# Sheet1.net
KiCad netlist of a schematic drawn in Altium Designer
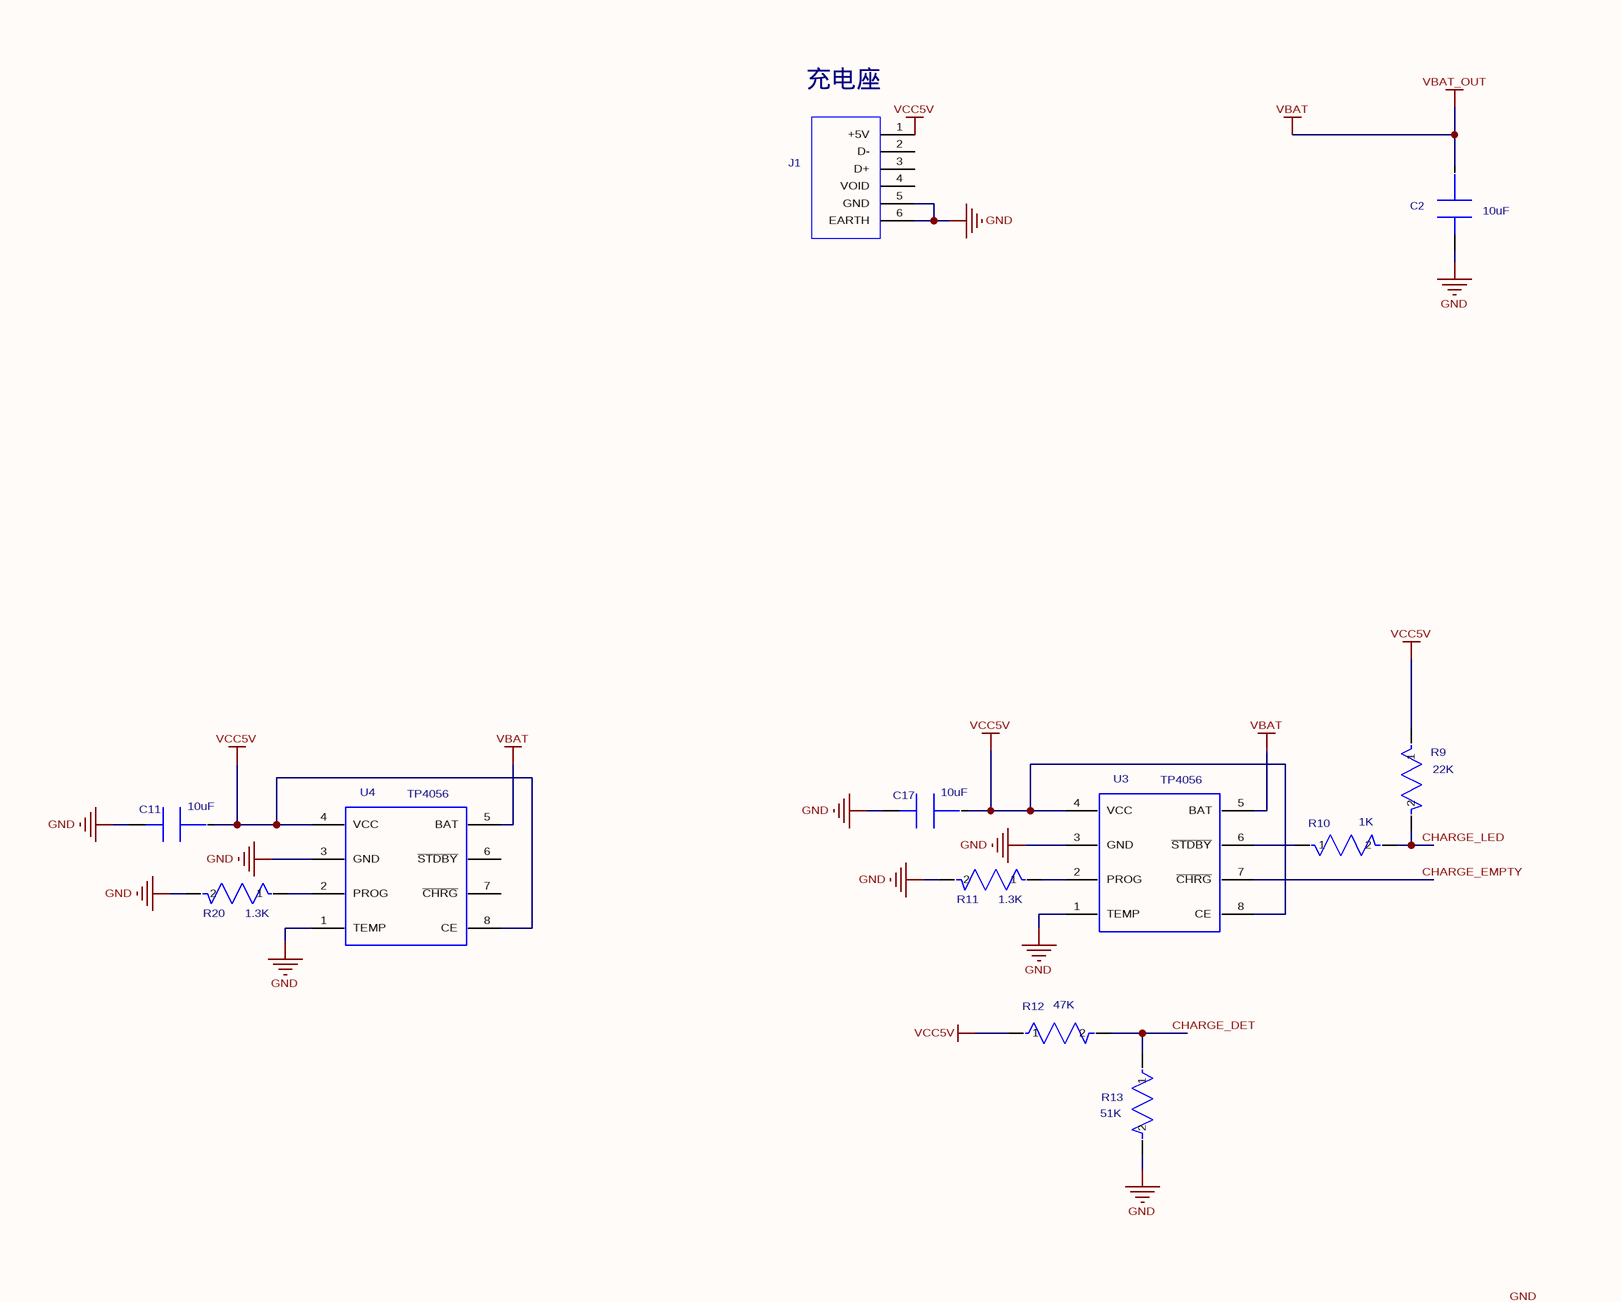
[diagram p0: Sheet1.SchDoc, top column 1 of 4]
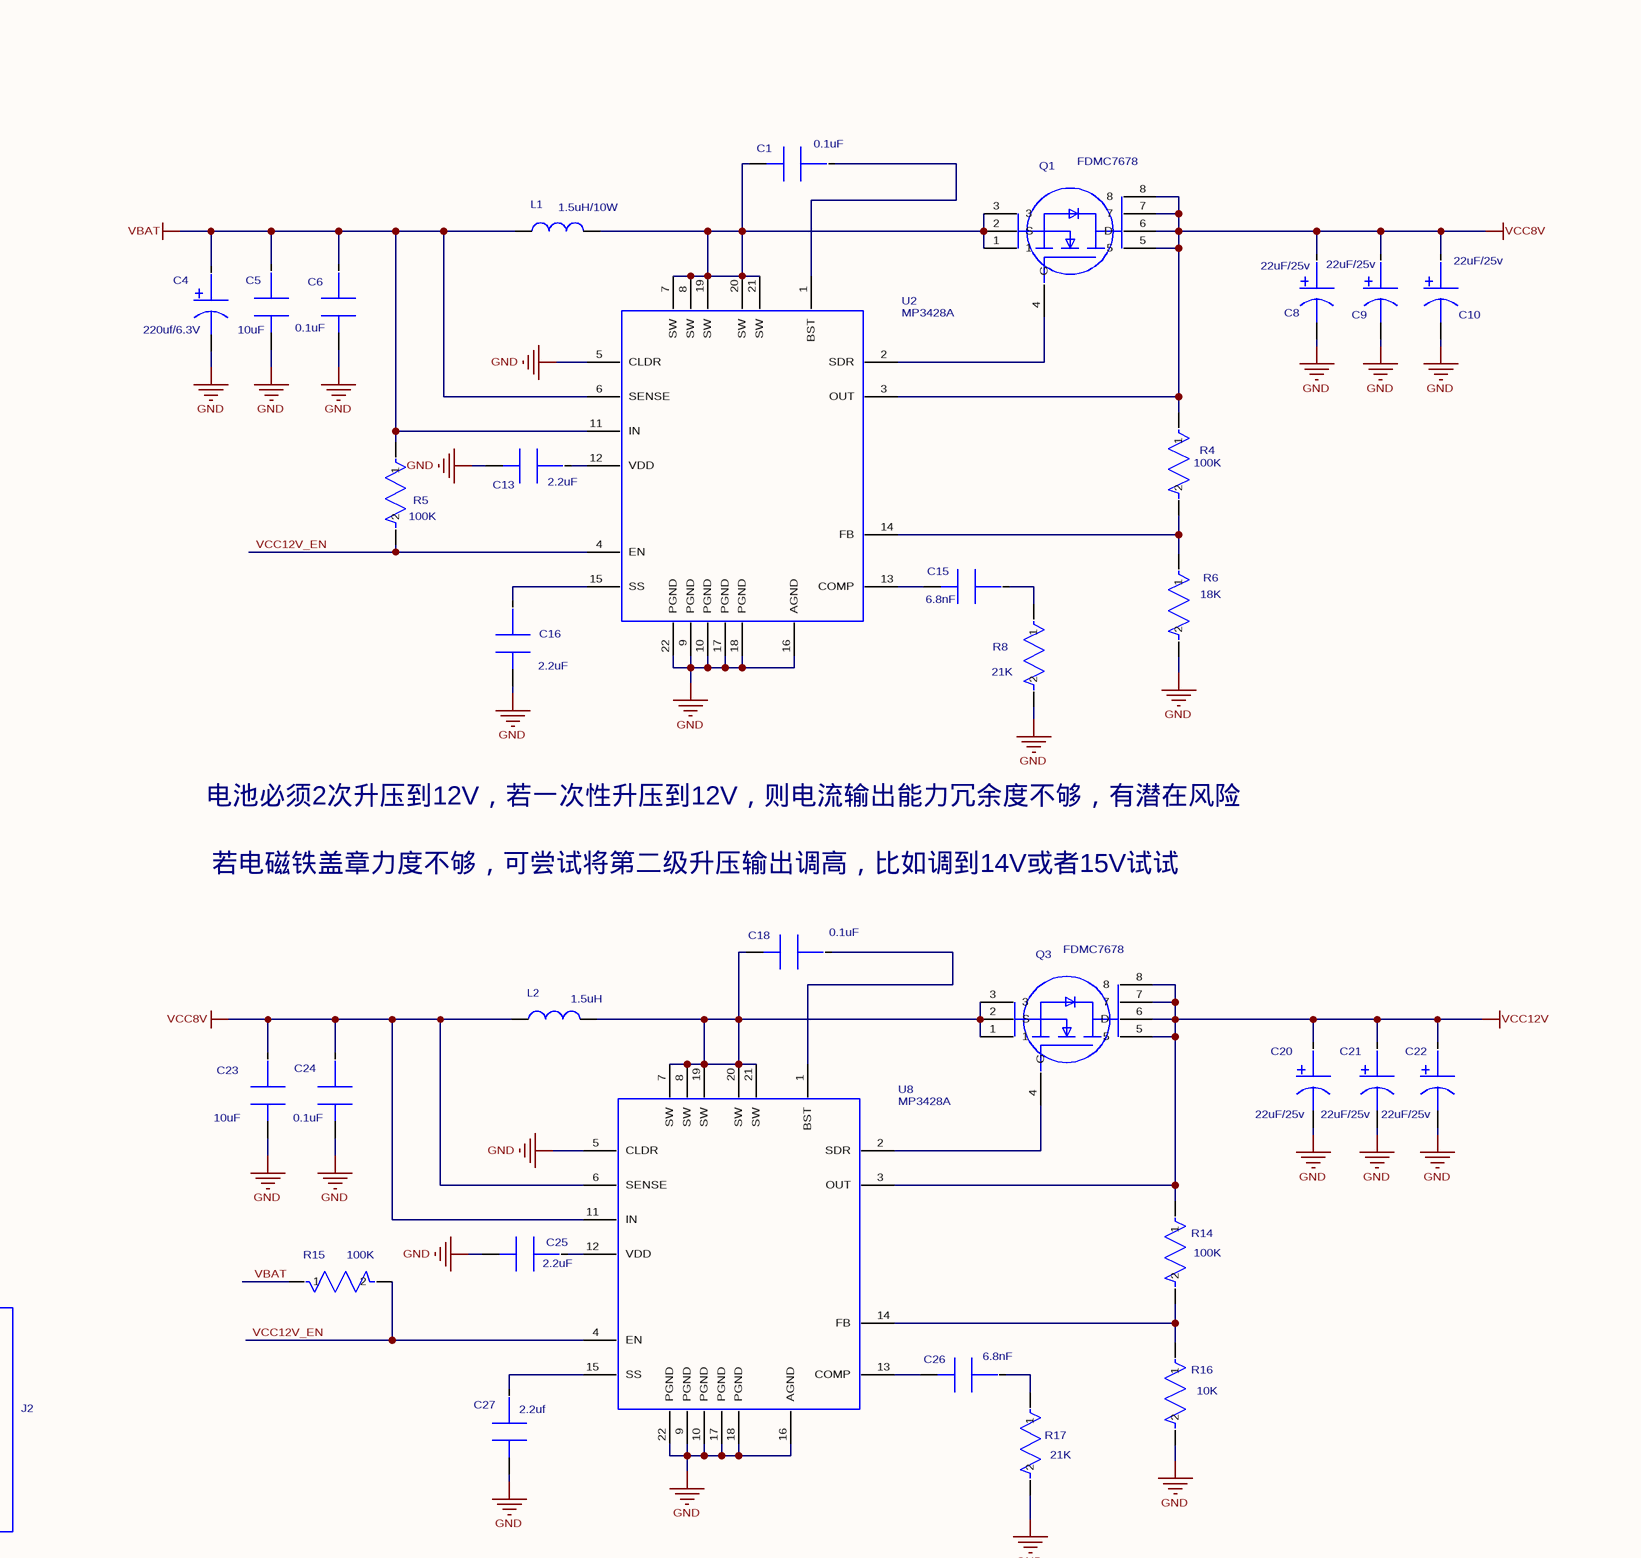
[diagram p1: Sheet1.SchDoc, top column 2 of 4]
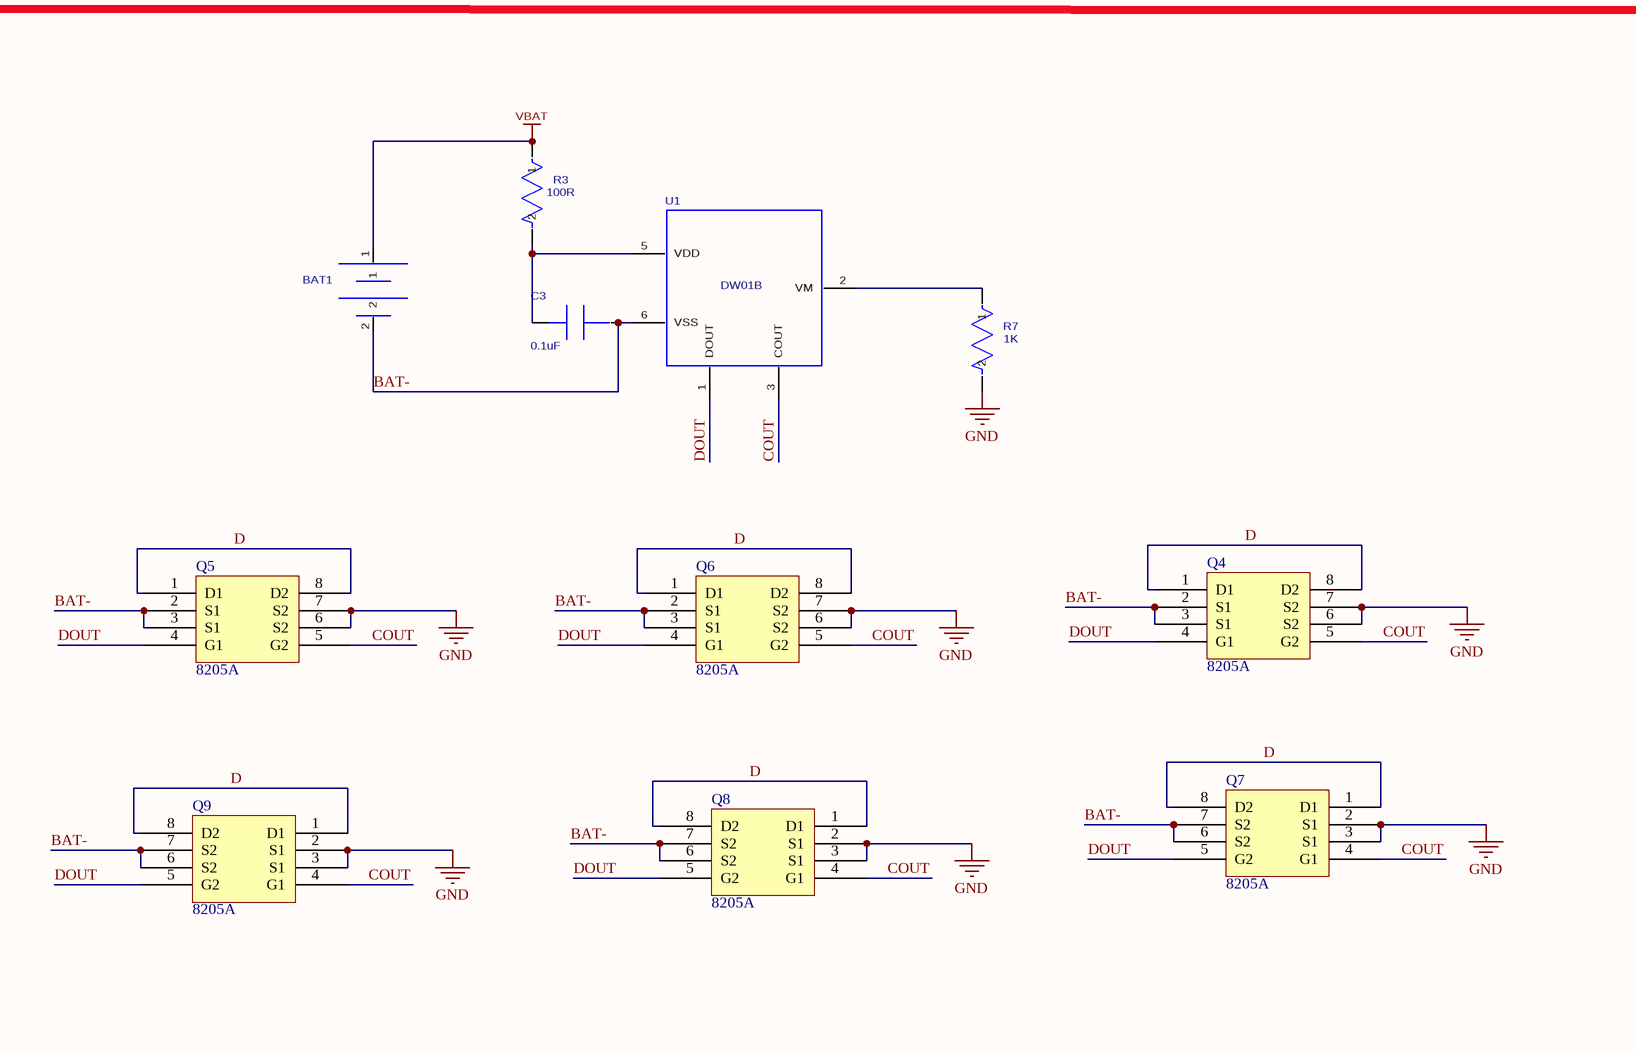
[diagram p2: Sheet1.SchDoc, top column 4 of 4]
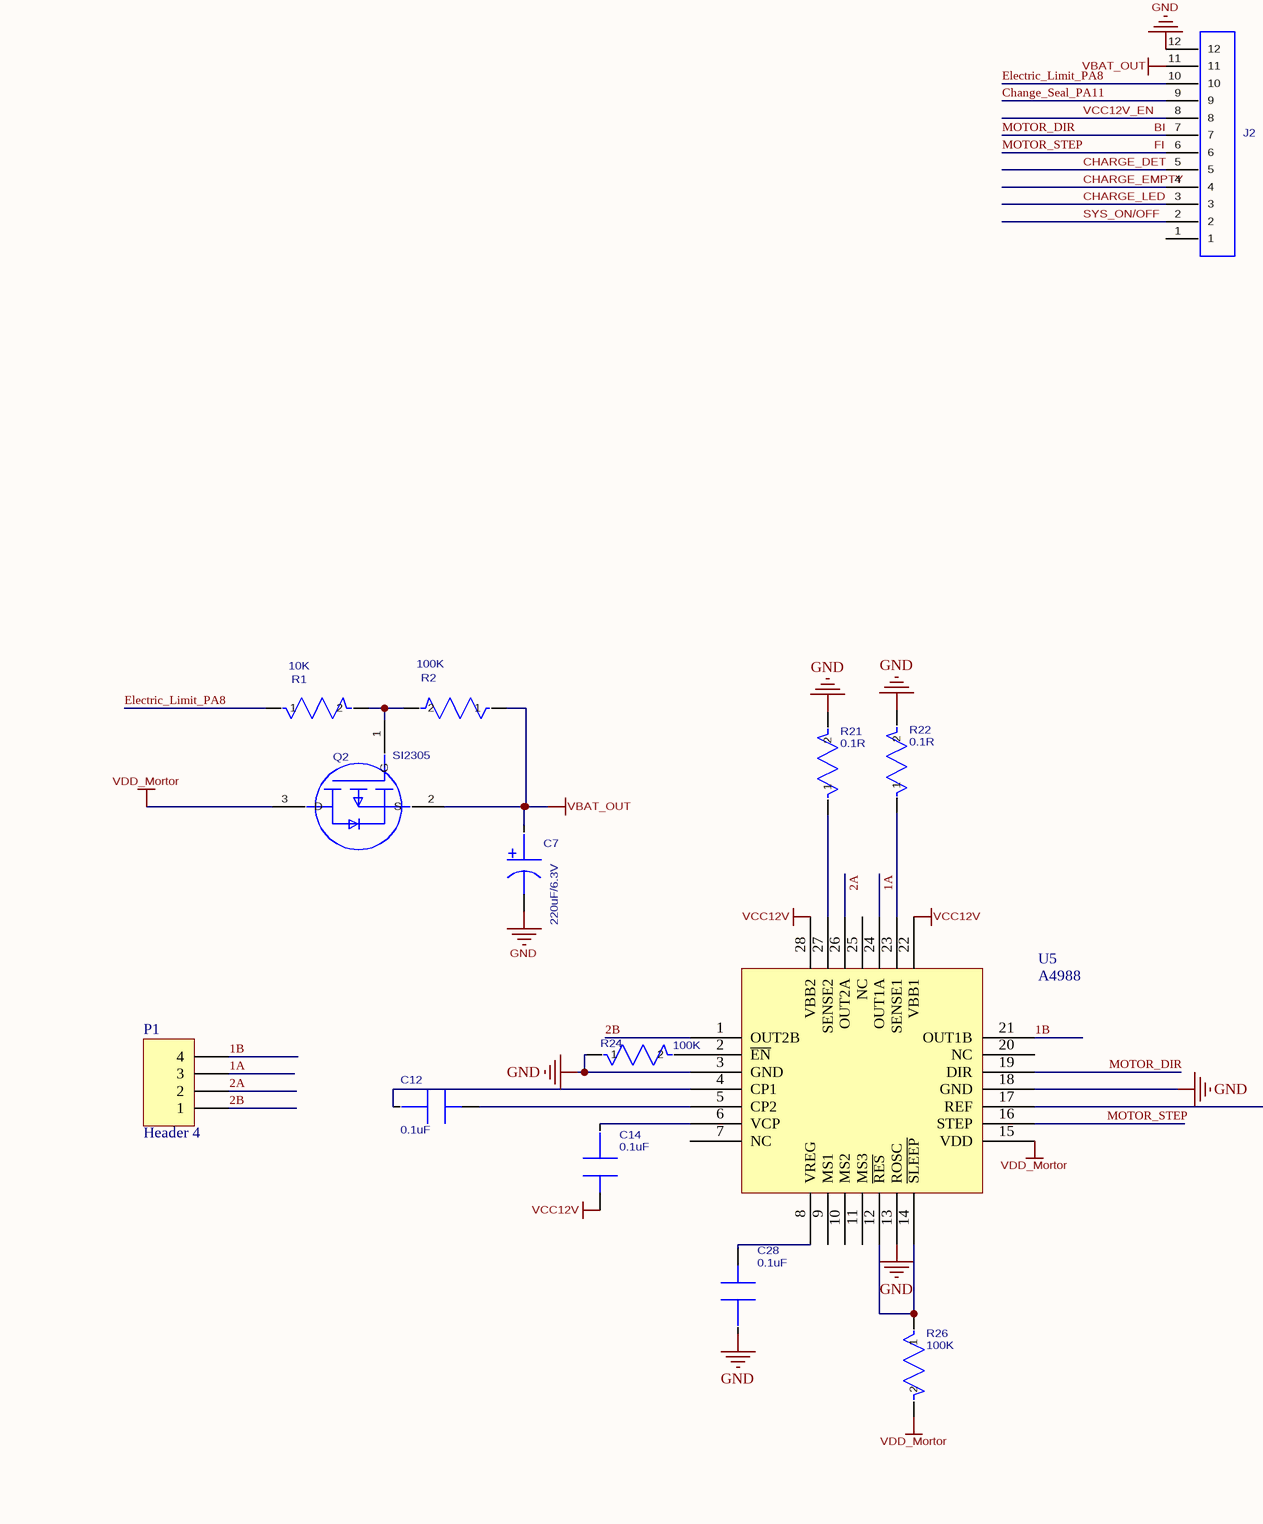
[diagram p3: Sheet1.SchDoc, bottom column 1 of 4]
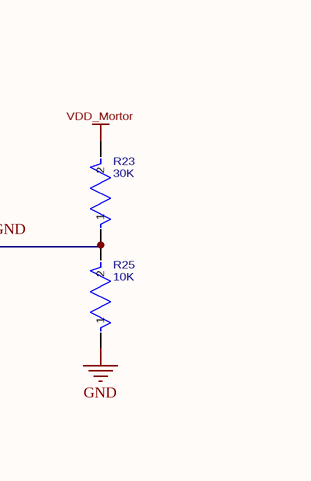
[diagram p4: Sheet1.SchDoc, bottom column 2 of 4]
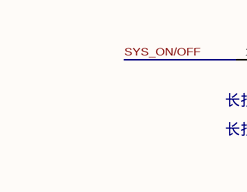
[diagram p5: Sheet1.SchDoc, bottom column 3 of 4]
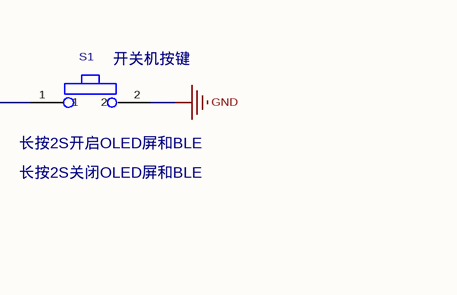
[diagram p6: Sheet1.SchDoc, bottom column 4 of 4]

(export (version "E")
  (design (tool "Eeschema 10.0.6"))
  (components
    (comp (ref "BAT1") (value "BAT1") (footprint "BAT18650_DIP2") (libsource (lib "*") (part "BAT1")))
    (comp (ref "C1") (value "0.1uF") (footprint "C0603") (libsource (lib "*") (part "C")))
    (comp (ref "C2") (value "10uF") (footprint "C0603") (libsource (lib "*") (part "C")))
    (comp (ref "C3") (value "0.1uF") (footprint "C0603") (libsource (lib "*") (part "C")))
    (comp (ref "C4") (value "220uf/6.3V") (footprint "C1210-E") (libsource (lib "") (part "C_1")))
    (comp (ref "C5") (value "10uF") (footprint "C0603") (libsource (lib "*") (part "C")))
    (comp (ref "C6") (value "0.1uF") (footprint "C0603") (libsource (lib "*") (part "C")))
    (comp (ref "C7") (value "220uF/6.3V") (footprint "C1210-E") (libsource (lib "") (part "C_1")))
    (comp (ref "C8") (value "22uF/25v") (footprint "C1210-E") (libsource (lib "") (part "C_1")))
    (comp (ref "C9") (value "22uF/25v") (footprint "C1210-E") (libsource (lib "") (part "C_1")))
    (comp (ref "C10") (value "22uF/25v") (footprint "C1210-E") (libsource (lib "") (part "C_1")))
    (comp (ref "C11") (value "10uF") (footprint "C0603") (libsource (lib "*") (part "C")))
    (comp (ref "C12") (value "0.1uF") (footprint "C0603") (libsource (lib "*") (part "C")))
    (comp (ref "C13") (value "2.2uF") (footprint "C0603") (libsource (lib "*") (part "C")))
    (comp (ref "C14") (value "0.1uF") (footprint "C0603") (libsource (lib "*") (part "C")))
    (comp (ref "C15") (value "6.8nF") (footprint "C0603") (libsource (lib "*") (part "C")))
    (comp (ref "C16") (value "2.2uF") (footprint "C0603") (libsource (lib "*") (part "C")))
    (comp (ref "C17") (value "10uF") (footprint "C0603") (libsource (lib "*") (part "C")))
    (comp (ref "C18") (value "0.1uF") (footprint "C0603") (libsource (lib "*") (part "C")))
    (comp (ref "C20") (value "22uF/25v") (footprint "C1210-E") (libsource (lib "") (part "C_1")))
    (comp (ref "C21") (value "22uF/25v") (footprint "C1210-E") (libsource (lib "") (part "C_1")))
    (comp (ref "C22") (value "22uF/25v") (footprint "CAP12R5X30") (libsource (lib "") (part "C_1")))
    (comp (ref "C23") (value "10uF") (footprint "C0603") (libsource (lib "*") (part "C")))
    (comp (ref "C24") (value "0.1uF") (footprint "C0603") (libsource (lib "*") (part "C")))
    (comp (ref "C25") (value "2.2uF") (footprint "C0603") (libsource (lib "*") (part "C")))
    (comp (ref "C26") (value "6.8nF") (footprint "C0603") (libsource (lib "*") (part "C")))
    (comp (ref "C27") (value "2.2uf") (footprint "C0603") (libsource (lib "*") (part "C")))
    (comp (ref "C28") (value "0.1uF") (footprint "C0603") (libsource (lib "*") (part "C")))
    (comp (ref "J1") (value "HEADER_6_2") (footprint "MICRO_USB_J") (libsource (lib "*") (part "HEADER_6_2")))
    (comp (ref "J2") (value "CON12") (footprint "CON_12WT") (libsource (lib "*") (part "CON12")))
    (comp (ref "L1") (value "1.5uH/10W") (footprint "L0630") (libsource (lib "*") (part "L")))
    (comp (ref "L2") (value "1.5uH") (footprint "L0630") (libsource (lib "*") (part "L")))
    (comp (ref "P1")
      (value "Header 4")
      (footprint "HDR1X4")
      (description "Header, 4-Pin")
      (fields (field (name "PUBLISHER") "Altium Limited"))
      (libsource (lib "Miscellaneous Connectors") (part "Header 4"))
    )
    (comp (ref "Q1") (value "FDMC7678") (footprint "FDMC7678") (libsource (lib "*") (part "FDMC7678")))
    (comp (ref "Q2") (value "SI2305") (footprint "SOT23") (libsource (lib "*") (part "FDN338P")))
    (comp (ref "Q3") (value "FDMC7678") (footprint "FDMC7678") (libsource (lib "*") (part "FDMC7678")))
    (comp (ref "Q4")
      (value "8205A")
      (footprint "TSSOP8")
      (libsource (lib "PCB_Project") (part "8205A-TSSOP8"))
    )
    (comp (ref "Q5")
      (value "8205A")
      (footprint "TSSOP8")
      (libsource (lib "PCB_Project") (part "8205A-TSSOP8"))
    )
    (comp (ref "Q6")
      (value "8205A")
      (footprint "TSSOP8")
      (libsource (lib "PCB_Project") (part "8205A-TSSOP8"))
    )
    (comp (ref "Q7") (value "8205A") (footprint "TSSOP8") (libsource (lib "") (part "8205A-TSSOP8_1")))
    (comp (ref "Q8") (value "8205A") (footprint "TSSOP8") (libsource (lib "") (part "8205A-TSSOP8_1")))
    (comp (ref "Q9") (value "8205A") (footprint "TSSOP8") (libsource (lib "") (part "8205A-TSSOP8_1")))
    (comp (ref "R1") (value "10K") (footprint "R0603") (libsource (lib "*") (part "R")))
    (comp (ref "R2") (value "100K") (footprint "R0603") (libsource (lib "*") (part "R")))
    (comp (ref "R3") (value "100R") (footprint "R0603") (libsource (lib "*") (part "R")))
    (comp (ref "R4") (value "100K") (footprint "R0603") (libsource (lib "*") (part "R")))
    (comp (ref "R5") (value "100K") (footprint "R0603") (libsource (lib "*") (part "R")))
    (comp (ref "R6") (value "18K") (footprint "R0603") (libsource (lib "*") (part "R")))
    (comp (ref "R7") (value "1K") (footprint "R0603") (libsource (lib "*") (part "R")))
    (comp (ref "R8") (value "21K") (footprint "R0603") (libsource (lib "*") (part "R")))
    (comp (ref "R9") (value "22K") (footprint "R0603") (libsource (lib "*") (part "R")))
    (comp (ref "R10") (value "1K") (footprint "R0603") (libsource (lib "*") (part "R")))
    (comp (ref "R11") (value "1.3K") (footprint "R0603") (libsource (lib "*") (part "R")))
    (comp (ref "R12") (value "47K") (footprint "R0603") (libsource (lib "*") (part "R")))
    (comp (ref "R13") (value "51K") (footprint "R0603") (libsource (lib "*") (part "R")))
    (comp (ref "R14") (value "100K") (footprint "R0603") (libsource (lib "*") (part "R")))
    (comp (ref "R15") (value "100K") (footprint "R0603") (libsource (lib "*") (part "R")))
    (comp (ref "R16") (value "10K") (footprint "R0603") (libsource (lib "*") (part "R")))
    (comp (ref "R17") (value "21K") (footprint "R0603") (libsource (lib "*") (part "R")))
    (comp (ref "R20") (value "1.3K") (footprint "R0603") (libsource (lib "*") (part "R")))
    (comp (ref "R21") (value "0.1R") (footprint "R0805") (libsource (lib "*") (part "R")))
    (comp (ref "R22") (value "0.1R") (footprint "R0805") (libsource (lib "*") (part "R")))
    (comp (ref "R23") (value "30K") (footprint "R0603") (libsource (lib "*") (part "R")))
    (comp (ref "R24") (value "100K") (footprint "R0603") (libsource (lib "*") (part "R")))
    (comp (ref "R25") (value "10K") (footprint "R0603") (libsource (lib "*") (part "R")))
    (comp (ref "R26") (value "100K") (footprint "R0603") (libsource (lib "*") (part "R")))
    (comp (ref "S1") (value "SW_3X6X5") (footprint "SW3X6X3R5") (libsource (lib "*") (part "SW_3X6X5")))
    (comp (ref "U1") (value "DW01B") (footprint "SOT23-6") (libsource (lib "PCB_Project") (part "DW01V")))
    (comp (ref "U2") (value "MP3428A") (footprint "QFN22") (libsource (lib "PCB_Project") (part "MP3428A")))
    (comp (ref "U3") (value "TP4056") (footprint "SOIC8E") (libsource (lib "*") (part "TP4056")))
    (comp (ref "U4") (value "TP4056") (footprint "SOIC8E") (libsource (lib "*") (part "TP4056")))
    (comp (ref "U5") (value "A4988") (footprint "QFN28") (libsource (lib "PCB_Project") (part "A4988")))
    (comp (ref "U8") (value "MP3428A") (footprint "QFN22") (libsource (lib "PCB_Project") (part "MP3428A")))
  )
  (nets
    (net (code "1") (name "/1A") (class "Default")
      (node (ref "P1") (pin "3") (pinfunction "3_3") (pintype "passive"))
      (node (ref "U5") (pin "24") (pinfunction "OUT1A_24") (pintype "passive"))
    )
    (net (code "2") (name "/1B") (class "Default")
      (node (ref "P1") (pin "4") (pinfunction "4_4") (pintype "passive"))
      (node (ref "U5") (pin "21") (pinfunction "OUT1B_21") (pintype "passive"))
    )
    (net (code "3") (name "/2A") (class "Default")
      (node (ref "P1") (pin "2") (pinfunction "2_2") (pintype "passive"))
      (node (ref "U5") (pin "26") (pinfunction "OUT2A_26") (pintype "passive"))
    )
    (net (code "4") (name "/2B") (class "Default")
      (node (ref "P1") (pin "1") (pinfunction "1_1") (pintype "passive"))
      (node (ref "U5") (pin "1") (pinfunction "OUT2B_1") (pintype "passive"))
    )
    (net (code "5") (name "/BAT-") (class "Default")
      (node (ref "BAT1") (pin "2") (pinfunction "2_2") (pintype "passive"))
      (node (ref "C3") (pin "1") (pinfunction "1_1") (pintype "passive"))
      (node (ref "Q4") (pin "2") (pinfunction "S1_2") (pintype "passive"))
      (node (ref "Q4") (pin "3") (pinfunction "S1_3") (pintype "passive"))
      (node (ref "Q5") (pin "2") (pinfunction "S1_2") (pintype "passive"))
      (node (ref "Q5") (pin "3") (pinfunction "S1_3") (pintype "passive"))
      (node (ref "Q6") (pin "2") (pinfunction "S1_2") (pintype "passive"))
      (node (ref "Q6") (pin "3") (pinfunction "S1_3") (pintype "passive"))
      (node (ref "Q7") (pin "6") (pinfunction "S2_6") (pintype "passive"))
      (node (ref "Q7") (pin "7") (pinfunction "S2_7") (pintype "passive"))
      (node (ref "Q8") (pin "6") (pinfunction "S2_6") (pintype "passive"))
      (node (ref "Q8") (pin "7") (pinfunction "S2_7") (pintype "passive"))
      (node (ref "Q9") (pin "6") (pinfunction "S2_6") (pintype "passive"))
      (node (ref "Q9") (pin "7") (pinfunction "S2_7") (pintype "passive"))
      (node (ref "U1") (pin "6") (pinfunction "VSS_6") (pintype "passive"))
    )
    (net (code "6") (name "/BI") (class "Default")
      (node (ref "J2") (pin "7") (pinfunction "7_7") (pintype "passive"))
      (node (ref "U5") (pin "19") (pinfunction "DIR_19") (pintype "passive"))
    )
    (net (code "7") (name "/CHARGE_DET") (class "Default")
      (node (ref "J2") (pin "5") (pinfunction "5_5") (pintype "passive"))
      (node (ref "R12") (pin "2") (pinfunction "2_2") (pintype "passive"))
      (node (ref "R13") (pin "1") (pinfunction "1_1") (pintype "passive"))
    )
    (net (code "8") (name "/CHARGE_EMPTY") (class "Default")
      (node (ref "J2") (pin "4") (pinfunction "4_4") (pintype "passive"))
      (node (ref "U3") (pin "7") (pinfunction "CHRG_7") (pintype "passive"))
    )
    (net (code "9") (name "/CHARGE_LED") (class "Default")
      (node (ref "J2") (pin "3") (pinfunction "3_3") (pintype "passive"))
      (node (ref "R10") (pin "2") (pinfunction "2_2") (pintype "passive"))
      (node (ref "R9") (pin "2") (pinfunction "2_2") (pintype "passive"))
    )
    (net (code "10") (name "/COUT") (class "Default")
      (node (ref "Q4") (pin "5") (pinfunction "G2_5") (pintype "passive"))
      (node (ref "Q5") (pin "5") (pinfunction "G2_5") (pintype "passive"))
      (node (ref "Q6") (pin "5") (pinfunction "G2_5") (pintype "passive"))
      (node (ref "Q7") (pin "4") (pinfunction "G1_4") (pintype "passive"))
      (node (ref "Q8") (pin "4") (pinfunction "G1_4") (pintype "passive"))
      (node (ref "Q9") (pin "4") (pinfunction "G1_4") (pintype "passive"))
      (node (ref "U1") (pin "3") (pinfunction "COUT_3") (pintype "passive"))
    )
    (net (code "11") (name "/Change_Seal_PA11") (class "Default")
      (node (ref "J2") (pin "9") (pinfunction "9_9") (pintype "passive"))
    )
    (net (code "12") (name "/D") (class "Default")
      (node (ref "Q4") (pin "1") (pinfunction "D1_1") (pintype "passive"))
      (node (ref "Q4") (pin "8") (pinfunction "D2_8") (pintype "passive"))
      (node (ref "Q5") (pin "1") (pinfunction "D1_1") (pintype "passive"))
      (node (ref "Q5") (pin "8") (pinfunction "D2_8") (pintype "passive"))
      (node (ref "Q6") (pin "1") (pinfunction "D1_1") (pintype "passive"))
      (node (ref "Q6") (pin "8") (pinfunction "D2_8") (pintype "passive"))
      (node (ref "Q7") (pin "1") (pinfunction "D1_1") (pintype "passive"))
      (node (ref "Q7") (pin "8") (pinfunction "D2_8") (pintype "passive"))
      (node (ref "Q8") (pin "1") (pinfunction "D1_1") (pintype "passive"))
      (node (ref "Q8") (pin "8") (pinfunction "D2_8") (pintype "passive"))
      (node (ref "Q9") (pin "1") (pinfunction "D1_1") (pintype "passive"))
      (node (ref "Q9") (pin "8") (pinfunction "D2_8") (pintype "passive"))
    )
    (net (code "13") (name "/DOUT") (class "Default")
      (node (ref "Q4") (pin "4") (pinfunction "G1_4") (pintype "passive"))
      (node (ref "Q5") (pin "4") (pinfunction "G1_4") (pintype "passive"))
      (node (ref "Q6") (pin "4") (pinfunction "G1_4") (pintype "passive"))
      (node (ref "Q7") (pin "5") (pinfunction "G2_5") (pintype "passive"))
      (node (ref "Q8") (pin "5") (pinfunction "G2_5") (pintype "passive"))
      (node (ref "Q9") (pin "5") (pinfunction "G2_5") (pintype "passive"))
      (node (ref "U1") (pin "1") (pinfunction "DOUT_1") (pintype "passive"))
    )
    (net (code "14") (name "/Electric_Limit_PA8") (class "Default")
      (node (ref "J2") (pin "10") (pinfunction "10_10") (pintype "passive"))
      (node (ref "R1") (pin "1") (pinfunction "1_1") (pintype "passive"))
    )
    (net (code "15") (name "/FI") (class "Default")
      (node (ref "J2") (pin "6") (pinfunction "6_6") (pintype "passive"))
      (node (ref "U5") (pin "16") (pinfunction "STEP_16") (pintype "passive"))
    )
    (net (code "16") (name "/SYS_ON{slash}OFF") (class "Default")
      (node (ref "J2") (pin "2") (pinfunction "2_2") (pintype "passive"))
      (node (ref "S1") (pin "1") (pinfunction "1_1") (pintype "passive"))
    )
    (net (code "17") (name "/VCC12V_EN") (class "Default")
      (node (ref "J2") (pin "8") (pinfunction "8_8") (pintype "passive"))
      (node (ref "R15") (pin "2") (pinfunction "2_2") (pintype "passive"))
      (node (ref "R5") (pin "2") (pinfunction "2_2") (pintype "passive"))
      (node (ref "U2") (pin "4") (pinfunction "EN_4") (pintype "passive"))
      (node (ref "U8") (pin "4") (pinfunction "EN_4") (pintype "passive"))
    )
    (net (code "18") (name "GND") (class "Default")
      (node (ref "C10") (pin "2") (pinfunction "2_2") (pintype "passive"))
      (node (ref "C11") (pin "2") (pinfunction "2_2") (pintype "passive"))
      (node (ref "C13") (pin "2") (pinfunction "2_2") (pintype "passive"))
      (node (ref "C16") (pin "2") (pinfunction "2_2") (pintype "passive"))
      (node (ref "C17") (pin "2") (pinfunction "2_2") (pintype "passive"))
      (node (ref "C2") (pin "2") (pinfunction "2_2") (pintype "passive"))
      (node (ref "C20") (pin "2") (pinfunction "2_2") (pintype "passive"))
      (node (ref "C21") (pin "2") (pinfunction "2_2") (pintype "passive"))
      (node (ref "C22") (pin "2") (pinfunction "2_2") (pintype "passive"))
      (node (ref "C23") (pin "2") (pinfunction "2_2") (pintype "passive"))
      (node (ref "C24") (pin "2") (pinfunction "2_2") (pintype "passive"))
      (node (ref "C25") (pin "2") (pinfunction "2_2") (pintype "passive"))
      (node (ref "C27") (pin "2") (pinfunction "2_2") (pintype "passive"))
      (node (ref "C28") (pin "1") (pinfunction "1_1") (pintype "passive"))
      (node (ref "C4") (pin "2") (pinfunction "2_2") (pintype "passive"))
      (node (ref "C5") (pin "2") (pinfunction "2_2") (pintype "passive"))
      (node (ref "C6") (pin "2") (pinfunction "2_2") (pintype "passive"))
      (node (ref "C7") (pin "2") (pinfunction "2_2") (pintype "passive"))
      (node (ref "C8") (pin "2") (pinfunction "2_2") (pintype "passive"))
      (node (ref "C9") (pin "2") (pinfunction "2_2") (pintype "passive"))
      (node (ref "J1") (pin "5") (pinfunction "GND_5") (pintype "passive"))
      (node (ref "J1") (pin "6") (pinfunction "EARTH_6") (pintype "passive"))
      (node (ref "J2") (pin "12") (pinfunction "12_12") (pintype "passive"))
      (node (ref "Q4") (pin "6") (pinfunction "S2_6") (pintype "passive"))
      (node (ref "Q4") (pin "7") (pinfunction "S2_7") (pintype "passive"))
      (node (ref "Q5") (pin "6") (pinfunction "S2_6") (pintype "passive"))
      (node (ref "Q5") (pin "7") (pinfunction "S2_7") (pintype "passive"))
      (node (ref "Q6") (pin "6") (pinfunction "S2_6") (pintype "passive"))
      (node (ref "Q6") (pin "7") (pinfunction "S2_7") (pintype "passive"))
      (node (ref "Q7") (pin "2") (pinfunction "S1_2") (pintype "passive"))
      (node (ref "Q7") (pin "3") (pinfunction "S1_3") (pintype "passive"))
      (node (ref "Q8") (pin "2") (pinfunction "S1_2") (pintype "passive"))
      (node (ref "Q8") (pin "3") (pinfunction "S1_3") (pintype "passive"))
      (node (ref "Q9") (pin "2") (pinfunction "S1_2") (pintype "passive"))
      (node (ref "Q9") (pin "3") (pinfunction "S1_3") (pintype "passive"))
      (node (ref "R11") (pin "2") (pinfunction "2_2") (pintype "passive"))
      (node (ref "R13") (pin "2") (pinfunction "2_2") (pintype "passive"))
      (node (ref "R16") (pin "2") (pinfunction "2_2") (pintype "passive"))
      (node (ref "R17") (pin "2") (pinfunction "2_2") (pintype "passive"))
      (node (ref "R20") (pin "2") (pinfunction "2_2") (pintype "passive"))
      (node (ref "R21") (pin "2") (pinfunction "2_2") (pintype "passive"))
      (node (ref "R22") (pin "2") (pinfunction "2_2") (pintype "passive"))
      (node (ref "R24") (pin "1") (pinfunction "1_1") (pintype "passive"))
      (node (ref "R25") (pin "1") (pinfunction "1_1") (pintype "passive"))
      (node (ref "R6") (pin "2") (pinfunction "2_2") (pintype "passive"))
      (node (ref "R7") (pin "2") (pinfunction "2_2") (pintype "passive"))
      (node (ref "R8") (pin "2") (pinfunction "2_2") (pintype "passive"))
      (node (ref "S1") (pin "2") (pinfunction "2_2") (pintype "passive"))
      (node (ref "U2") (pin "10") (pinfunction "PGND_10") (pintype "passive"))
      (node (ref "U2") (pin "16") (pinfunction "AGND_16") (pintype "passive"))
      (node (ref "U2") (pin "17") (pinfunction "PGND_17") (pintype "passive"))
      (node (ref "U2") (pin "18") (pinfunction "PGND_18") (pintype "passive"))
      (node (ref "U2") (pin "22") (pinfunction "PGND_22") (pintype "passive"))
      (node (ref "U2") (pin "5") (pinfunction "CLDR_5") (pintype "passive"))
      (node (ref "U2") (pin "9") (pinfunction "PGND_9") (pintype "passive"))
      (node (ref "U3") (pin "1") (pinfunction "TEMP_1") (pintype "passive"))
      (node (ref "U3") (pin "3") (pinfunction "GND_3") (pintype "passive"))
      (node (ref "U4") (pin "1") (pinfunction "TEMP_1") (pintype "passive"))
      (node (ref "U4") (pin "3") (pinfunction "GND_3") (pintype "passive"))
      (node (ref "U5") (pin "13") (pinfunction "ROSC_13") (pintype "passive"))
      (node (ref "U5") (pin "18") (pinfunction "GND_18") (pintype "passive"))
      (node (ref "U5") (pin "3") (pinfunction "GND_3") (pintype "passive"))
      (node (ref "U8") (pin "10") (pinfunction "PGND_10") (pintype "passive"))
      (node (ref "U8") (pin "16") (pinfunction "AGND_16") (pintype "passive"))
      (node (ref "U8") (pin "17") (pinfunction "PGND_17") (pintype "passive"))
      (node (ref "U8") (pin "18") (pinfunction "PGND_18") (pintype "passive"))
      (node (ref "U8") (pin "22") (pinfunction "PGND_22") (pintype "passive"))
      (node (ref "U8") (pin "5") (pinfunction "CLDR_5") (pintype "passive"))
      (node (ref "U8") (pin "9") (pinfunction "PGND_9") (pintype "passive"))
    )
    (net (code "19") (name "Net-(C15-Pad1)") (class "Default")
      (node (ref "C15") (pin "1") (pinfunction "1_1") (pintype "passive"))
      (node (ref "R8") (pin "1") (pinfunction "1_1") (pintype "passive"))
    )
    (net (code "20") (name "Net-(C26-Pad1)") (class "Default")
      (node (ref "C26") (pin "1") (pinfunction "1_1") (pintype "passive"))
      (node (ref "R17") (pin "1") (pinfunction "1_1") (pintype "passive"))
    )
    (net (code "21") (name "Net-(Q1-G)") (class "Default")
      (node (ref "Q1") (pin "4") (pinfunction "G_4") (pintype "passive"))
      (node (ref "U2") (pin "2") (pinfunction "SDR_2") (pintype "passive"))
    )
    (net (code "22") (name "Net-(Q1-S)") (class "Default")
      (node (ref "C1") (pin "2") (pinfunction "2_2") (pintype "passive"))
      (node (ref "L1") (pin "2") (pinfunction "2_2") (pintype "passive"))
      (node (ref "Q1") (pin "1") (pinfunction "1_1") (pintype "passive"))
      (node (ref "Q1") (pin "2") (pinfunction "S_2") (pintype "passive"))
      (node (ref "Q1") (pin "3") (pinfunction "3_3") (pintype "passive"))
      (node (ref "U2") (pin "19") (pinfunction "SW_19") (pintype "passive"))
      (node (ref "U2") (pin "20") (pinfunction "SW_20") (pintype "passive"))
      (node (ref "U2") (pin "21") (pinfunction "SW_21") (pintype "passive"))
      (node (ref "U2") (pin "7") (pinfunction "SW_7") (pintype "passive"))
      (node (ref "U2") (pin "8") (pinfunction "SW_8") (pintype "passive"))
    )
    (net (code "23") (name "Net-(Q2-G)") (class "Default")
      (node (ref "Q2") (pin "1") (pinfunction "G_1") (pintype "passive"))
      (node (ref "R1") (pin "2") (pinfunction "2_2") (pintype "passive"))
      (node (ref "R2") (pin "2") (pinfunction "2_2") (pintype "passive"))
    )
    (net (code "24") (name "Net-(Q3-G)") (class "Default")
      (node (ref "Q3") (pin "4") (pinfunction "G_4") (pintype "passive"))
      (node (ref "U8") (pin "2") (pinfunction "SDR_2") (pintype "passive"))
    )
    (net (code "25") (name "Net-(Q3-S)") (class "Default")
      (node (ref "C18") (pin "2") (pinfunction "2_2") (pintype "passive"))
      (node (ref "L2") (pin "2") (pinfunction "2_2") (pintype "passive"))
      (node (ref "Q3") (pin "1") (pinfunction "1_1") (pintype "passive"))
      (node (ref "Q3") (pin "2") (pinfunction "S_2") (pintype "passive"))
      (node (ref "Q3") (pin "3") (pinfunction "3_3") (pintype "passive"))
      (node (ref "U8") (pin "19") (pinfunction "SW_19") (pintype "passive"))
      (node (ref "U8") (pin "20") (pinfunction "SW_20") (pintype "passive"))
      (node (ref "U8") (pin "21") (pinfunction "SW_21") (pintype "passive"))
      (node (ref "U8") (pin "7") (pinfunction "SW_7") (pintype "passive"))
      (node (ref "U8") (pin "8") (pinfunction "SW_8") (pintype "passive"))
    )
    (net (code "26") (name "Net-(U1-VDD)") (class "Default")
      (node (ref "C3") (pin "2") (pinfunction "2_2") (pintype "passive"))
      (node (ref "R3") (pin "2") (pinfunction "2_2") (pintype "passive"))
      (node (ref "U1") (pin "5") (pinfunction "VDD_5") (pintype "passive"))
    )
    (net (code "27") (name "Net-(U1-VM)") (class "Default")
      (node (ref "R7") (pin "1") (pinfunction "1_1") (pintype "passive"))
      (node (ref "U1") (pin "2") (pinfunction "VM_2") (pintype "passive"))
    )
    (net (code "28") (name "Net-(U2-BST)") (class "Default")
      (node (ref "C1") (pin "1") (pinfunction "1_1") (pintype "passive"))
      (node (ref "U2") (pin "1") (pinfunction "BST_1") (pintype "passive"))
    )
    (net (code "29") (name "Net-(U2-COMP)") (class "Default")
      (node (ref "C15") (pin "2") (pinfunction "2_2") (pintype "passive"))
      (node (ref "U2") (pin "13") (pinfunction "COMP_13") (pintype "passive"))
    )
    (net (code "30") (name "Net-(U2-FB)") (class "Default")
      (node (ref "R4") (pin "2") (pinfunction "2_2") (pintype "passive"))
      (node (ref "R6") (pin "1") (pinfunction "1_1") (pintype "passive"))
      (node (ref "U2") (pin "14") (pinfunction "FB_14") (pintype "passive"))
    )
    (net (code "31") (name "Net-(U2-SS)") (class "Default")
      (node (ref "C16") (pin "1") (pinfunction "1_1") (pintype "passive"))
      (node (ref "U2") (pin "15") (pinfunction "SS_15") (pintype "passive"))
    )
    (net (code "32") (name "Net-(U2-VDD)") (class "Default")
      (node (ref "C13") (pin "1") (pinfunction "1_1") (pintype "passive"))
      (node (ref "U2") (pin "12") (pinfunction "VDD_12") (pintype "passive"))
    )
    (net (code "33") (name "Net-(U3-PROG)") (class "Default")
      (node (ref "R11") (pin "1") (pinfunction "1_1") (pintype "passive"))
      (node (ref "U3") (pin "2") (pinfunction "PROG_2") (pintype "passive"))
    )
    (net (code "34") (name "Net-(U3-STDBY)") (class "Default")
      (node (ref "R10") (pin "1") (pinfunction "1_1") (pintype "passive"))
      (node (ref "U3") (pin "6") (pinfunction "STDBY_6") (pintype "passive"))
    )
    (net (code "35") (name "Net-(U4-PROG)") (class "Default")
      (node (ref "R20") (pin "1") (pinfunction "1_1") (pintype "passive"))
      (node (ref "U4") (pin "2") (pinfunction "PROG_2") (pintype "passive"))
    )
    (net (code "36") (name "Net-(U5-CP1)") (class "Default")
      (node (ref "C12") (pin "1") (pinfunction "1_1") (pintype "passive"))
      (node (ref "U5") (pin "4") (pinfunction "CP1_4") (pintype "passive"))
    )
    (net (code "37") (name "Net-(U5-CP2)") (class "Default")
      (node (ref "C12") (pin "2") (pinfunction "2_2") (pintype "passive"))
      (node (ref "U5") (pin "5") (pinfunction "CP2_5") (pintype "passive"))
    )
    (net (code "38") (name "Net-(U5-REF)") (class "Default")
      (node (ref "R23") (pin "1") (pinfunction "1_1") (pintype "passive"))
      (node (ref "R25") (pin "2") (pinfunction "2_2") (pintype "passive"))
      (node (ref "U5") (pin "17") (pinfunction "REF_17") (pintype "passive"))
    )
    (net (code "39") (name "Net-(U5-SENSE1)") (class "Default")
      (node (ref "R22") (pin "1") (pinfunction "1_1") (pintype "passive"))
      (node (ref "U5") (pin "23") (pinfunction "SENSE1_23") (pintype "passive"))
    )
    (net (code "40") (name "Net-(U5-SENSE2)") (class "Default")
      (node (ref "R21") (pin "1") (pinfunction "1_1") (pintype "passive"))
      (node (ref "U5") (pin "27") (pinfunction "SENSE2_27") (pintype "passive"))
    )
    (net (code "41") (name "Net-(U5-VCP)") (class "Default")
      (node (ref "C14") (pin "1") (pinfunction "1_1") (pintype "passive"))
      (node (ref "U5") (pin "6") (pinfunction "VCP_6") (pintype "passive"))
    )
    (net (code "42") (name "Net-(U5-VREG)") (class "Default")
      (node (ref "C28") (pin "2") (pinfunction "2_2") (pintype "passive"))
      (node (ref "U5") (pin "8") (pinfunction "VREG_8") (pintype "passive"))
    )
    (net (code "43") (name "Net-(U5-~{EN})") (class "Default")
      (node (ref "R24") (pin "2") (pinfunction "2_2") (pintype "passive"))
      (node (ref "U5") (pin "2") (pinfunction "~{EN}_2") (pintype "passive"))
    )
    (net (code "44") (name "Net-(U5-~{RES})") (class "Default")
      (node (ref "R26") (pin "1") (pinfunction "1_1") (pintype "passive"))
      (node (ref "U5") (pin "12") (pinfunction "~{RES}_12") (pintype "passive"))
      (node (ref "U5") (pin "14") (pinfunction "~{SLEEP}_14") (pintype "passive"))
    )
    (net (code "45") (name "Net-(U8-BST)") (class "Default")
      (node (ref "C18") (pin "1") (pinfunction "1_1") (pintype "passive"))
      (node (ref "U8") (pin "1") (pinfunction "BST_1") (pintype "passive"))
    )
    (net (code "46") (name "Net-(U8-COMP)") (class "Default")
      (node (ref "C26") (pin "2") (pinfunction "2_2") (pintype "passive"))
      (node (ref "U8") (pin "13") (pinfunction "COMP_13") (pintype "passive"))
    )
    (net (code "47") (name "Net-(U8-FB)") (class "Default")
      (node (ref "R14") (pin "2") (pinfunction "2_2") (pintype "passive"))
      (node (ref "R16") (pin "1") (pinfunction "1_1") (pintype "passive"))
      (node (ref "U8") (pin "14") (pinfunction "FB_14") (pintype "passive"))
    )
    (net (code "48") (name "Net-(U8-SS)") (class "Default")
      (node (ref "C27") (pin "1") (pinfunction "1_1") (pintype "passive"))
      (node (ref "U8") (pin "15") (pinfunction "SS_15") (pintype "passive"))
    )
    (net (code "49") (name "Net-(U8-VDD)") (class "Default")
      (node (ref "C25") (pin "1") (pinfunction "1_1") (pintype "passive"))
      (node (ref "U8") (pin "12") (pinfunction "VDD_12") (pintype "passive"))
    )
    (net (code "50") (name "VBAT") (class "Default")
      (node (ref "BAT1") (pin "1") (pinfunction "1_1") (pintype "passive"))
      (node (ref "C2") (pin "1") (pinfunction "1_1") (pintype "passive"))
      (node (ref "C4") (pin "1") (pinfunction "1_1") (pintype "passive"))
      (node (ref "C5") (pin "1") (pinfunction "1_1") (pintype "passive"))
      (node (ref "C6") (pin "1") (pinfunction "1_1") (pintype "passive"))
      (node (ref "C7") (pin "1") (pinfunction "1_1") (pintype "passive"))
      (node (ref "J2") (pin "11") (pinfunction "11_11") (pintype "passive"))
      (node (ref "L1") (pin "1") (pinfunction "1_1") (pintype "passive"))
      (node (ref "Q2") (pin "2") (pinfunction "S_2") (pintype "passive"))
      (node (ref "R15") (pin "1") (pinfunction "1_1") (pintype "passive"))
      (node (ref "R2") (pin "1") (pinfunction "1_1") (pintype "passive"))
      (node (ref "R3") (pin "1") (pinfunction "1_1") (pintype "passive"))
      (node (ref "R5") (pin "1") (pinfunction "1_1") (pintype "passive"))
      (node (ref "U2") (pin "11") (pinfunction "IN_11") (pintype "passive"))
      (node (ref "U2") (pin "6") (pinfunction "SENSE_6") (pintype "passive"))
      (node (ref "U3") (pin "5") (pinfunction "BAT_5") (pintype "passive"))
      (node (ref "U4") (pin "5") (pinfunction "BAT_5") (pintype "passive"))
    )
    (net (code "51") (name "VCC5V") (class "Default")
      (node (ref "C11") (pin "1") (pinfunction "1_1") (pintype "passive"))
      (node (ref "C17") (pin "1") (pinfunction "1_1") (pintype "passive"))
      (node (ref "J1") (pin "1") (pinfunction "+5V_1") (pintype "passive"))
      (node (ref "R12") (pin "1") (pinfunction "1_1") (pintype "passive"))
      (node (ref "R9") (pin "1") (pinfunction "1_1") (pintype "passive"))
      (node (ref "U3") (pin "4") (pinfunction "VCC_4") (pintype "passive"))
      (node (ref "U3") (pin "8") (pinfunction "CE_8") (pintype "passive"))
      (node (ref "U4") (pin "4") (pinfunction "VCC_4") (pintype "passive"))
      (node (ref "U4") (pin "8") (pinfunction "CE_8") (pintype "passive"))
    )
    (net (code "52") (name "VCC8V") (class "Default")
      (node (ref "C10") (pin "1") (pinfunction "1_1") (pintype "passive"))
      (node (ref "C23") (pin "1") (pinfunction "1_1") (pintype "passive"))
      (node (ref "C24") (pin "1") (pinfunction "1_1") (pintype "passive"))
      (node (ref "C8") (pin "1") (pinfunction "1_1") (pintype "passive"))
      (node (ref "C9") (pin "1") (pinfunction "1_1") (pintype "passive"))
      (node (ref "L2") (pin "1") (pinfunction "1_1") (pintype "passive"))
      (node (ref "Q1") (pin "5") (pinfunction "5_5") (pintype "passive"))
      (node (ref "Q1") (pin "6") (pinfunction "D_6") (pintype "passive"))
      (node (ref "Q1") (pin "7") (pinfunction "7_7") (pintype "passive"))
      (node (ref "Q1") (pin "8") (pinfunction "8_8") (pintype "passive"))
      (node (ref "R4") (pin "1") (pinfunction "1_1") (pintype "passive"))
      (node (ref "U2") (pin "3") (pinfunction "OUT_3") (pintype "passive"))
      (node (ref "U8") (pin "11") (pinfunction "IN_11") (pintype "passive"))
      (node (ref "U8") (pin "6") (pinfunction "SENSE_6") (pintype "passive"))
    )
    (net (code "53") (name "VCC12V") (class "Default")
      (node (ref "C14") (pin "2") (pinfunction "2_2") (pintype "passive"))
      (node (ref "C20") (pin "1") (pinfunction "1_1") (pintype "passive"))
      (node (ref "C21") (pin "1") (pinfunction "1_1") (pintype "passive"))
      (node (ref "C22") (pin "1") (pinfunction "1_1") (pintype "passive"))
      (node (ref "Q3") (pin "5") (pinfunction "5_5") (pintype "passive"))
      (node (ref "Q3") (pin "6") (pinfunction "D_6") (pintype "passive"))
      (node (ref "Q3") (pin "7") (pinfunction "7_7") (pintype "passive"))
      (node (ref "Q3") (pin "8") (pinfunction "8_8") (pintype "passive"))
      (node (ref "R14") (pin "1") (pinfunction "1_1") (pintype "passive"))
      (node (ref "U5") (pin "22") (pinfunction "VBB1_22") (pintype "passive"))
      (node (ref "U5") (pin "28") (pinfunction "VBB2_28") (pintype "passive"))
      (node (ref "U8") (pin "3") (pinfunction "OUT_3") (pintype "passive"))
    )
    (net (code "54") (name "VDD_Mortor") (class "Default")
      (node (ref "Q2") (pin "3") (pinfunction "D_3") (pintype "passive"))
      (node (ref "R23") (pin "2") (pinfunction "2_2") (pintype "passive"))
      (node (ref "R26") (pin "2") (pinfunction "2_2") (pintype "passive"))
      (node (ref "U5") (pin "15") (pinfunction "VDD_15") (pintype "passive"))
    )
    (net (code "55") (name "unconnected-(J1-D+-Pad3)") (class "Default")
      (node (ref "J1") (pin "3") (pinfunction "D+_3") (pintype "passive"))
    )
    (net (code "56") (name "unconnected-(J1-D--Pad2)") (class "Default")
      (node (ref "J1") (pin "2") (pinfunction "D-_2") (pintype "passive"))
    )
    (net (code "57") (name "unconnected-(J1-VOID-Pad4)") (class "Default")
      (node (ref "J1") (pin "4") (pinfunction "VOID_4") (pintype "passive"))
    )
    (net (code "58") (name "unconnected-(J2-Pad1)") (class "Default")
      (node (ref "J2") (pin "1") (pinfunction "1_1") (pintype "passive"))
    )
    (net (code "59") (name "unconnected-(U4-CHRG-Pad7)") (class "Default")
      (node (ref "U4") (pin "7") (pinfunction "CHRG_7") (pintype "passive"))
    )
    (net (code "60") (name "unconnected-(U4-STDBY-Pad6)") (class "Default")
      (node (ref "U4") (pin "6") (pinfunction "STDBY_6") (pintype "passive"))
    )
    (net (code "61") (name "unconnected-(U5-MS1-Pad9)") (class "Default")
      (node (ref "U5") (pin "9") (pinfunction "MS1_9") (pintype "passive"))
    )
    (net (code "62") (name "unconnected-(U5-MS2-Pad10)") (class "Default")
      (node (ref "U5") (pin "10") (pinfunction "MS2_10") (pintype "passive"))
    )
    (net (code "63") (name "unconnected-(U5-MS3-Pad11)") (class "Default")
      (node (ref "U5") (pin "11") (pinfunction "MS3_11") (pintype "passive"))
    )
    (net (code "64") (name "unconnected-(U5-NC-Pad7)") (class "Default")
      (node (ref "U5") (pin "7") (pinfunction "NC_7") (pintype "passive"))
    )
    (net (code "65") (name "unconnected-(U5-NC-Pad20)") (class "Default")
      (node (ref "U5") (pin "20") (pinfunction "NC_20") (pintype "passive"))
    )
    (net (code "66") (name "unconnected-(U5-NC-Pad25)") (class "Default")
      (node (ref "U5") (pin "25") (pinfunction "NC_25") (pintype "passive"))
    )
  )
)
